# Mighty_GCD.net
KiCad netlist of a schematic drawn in EAGLE
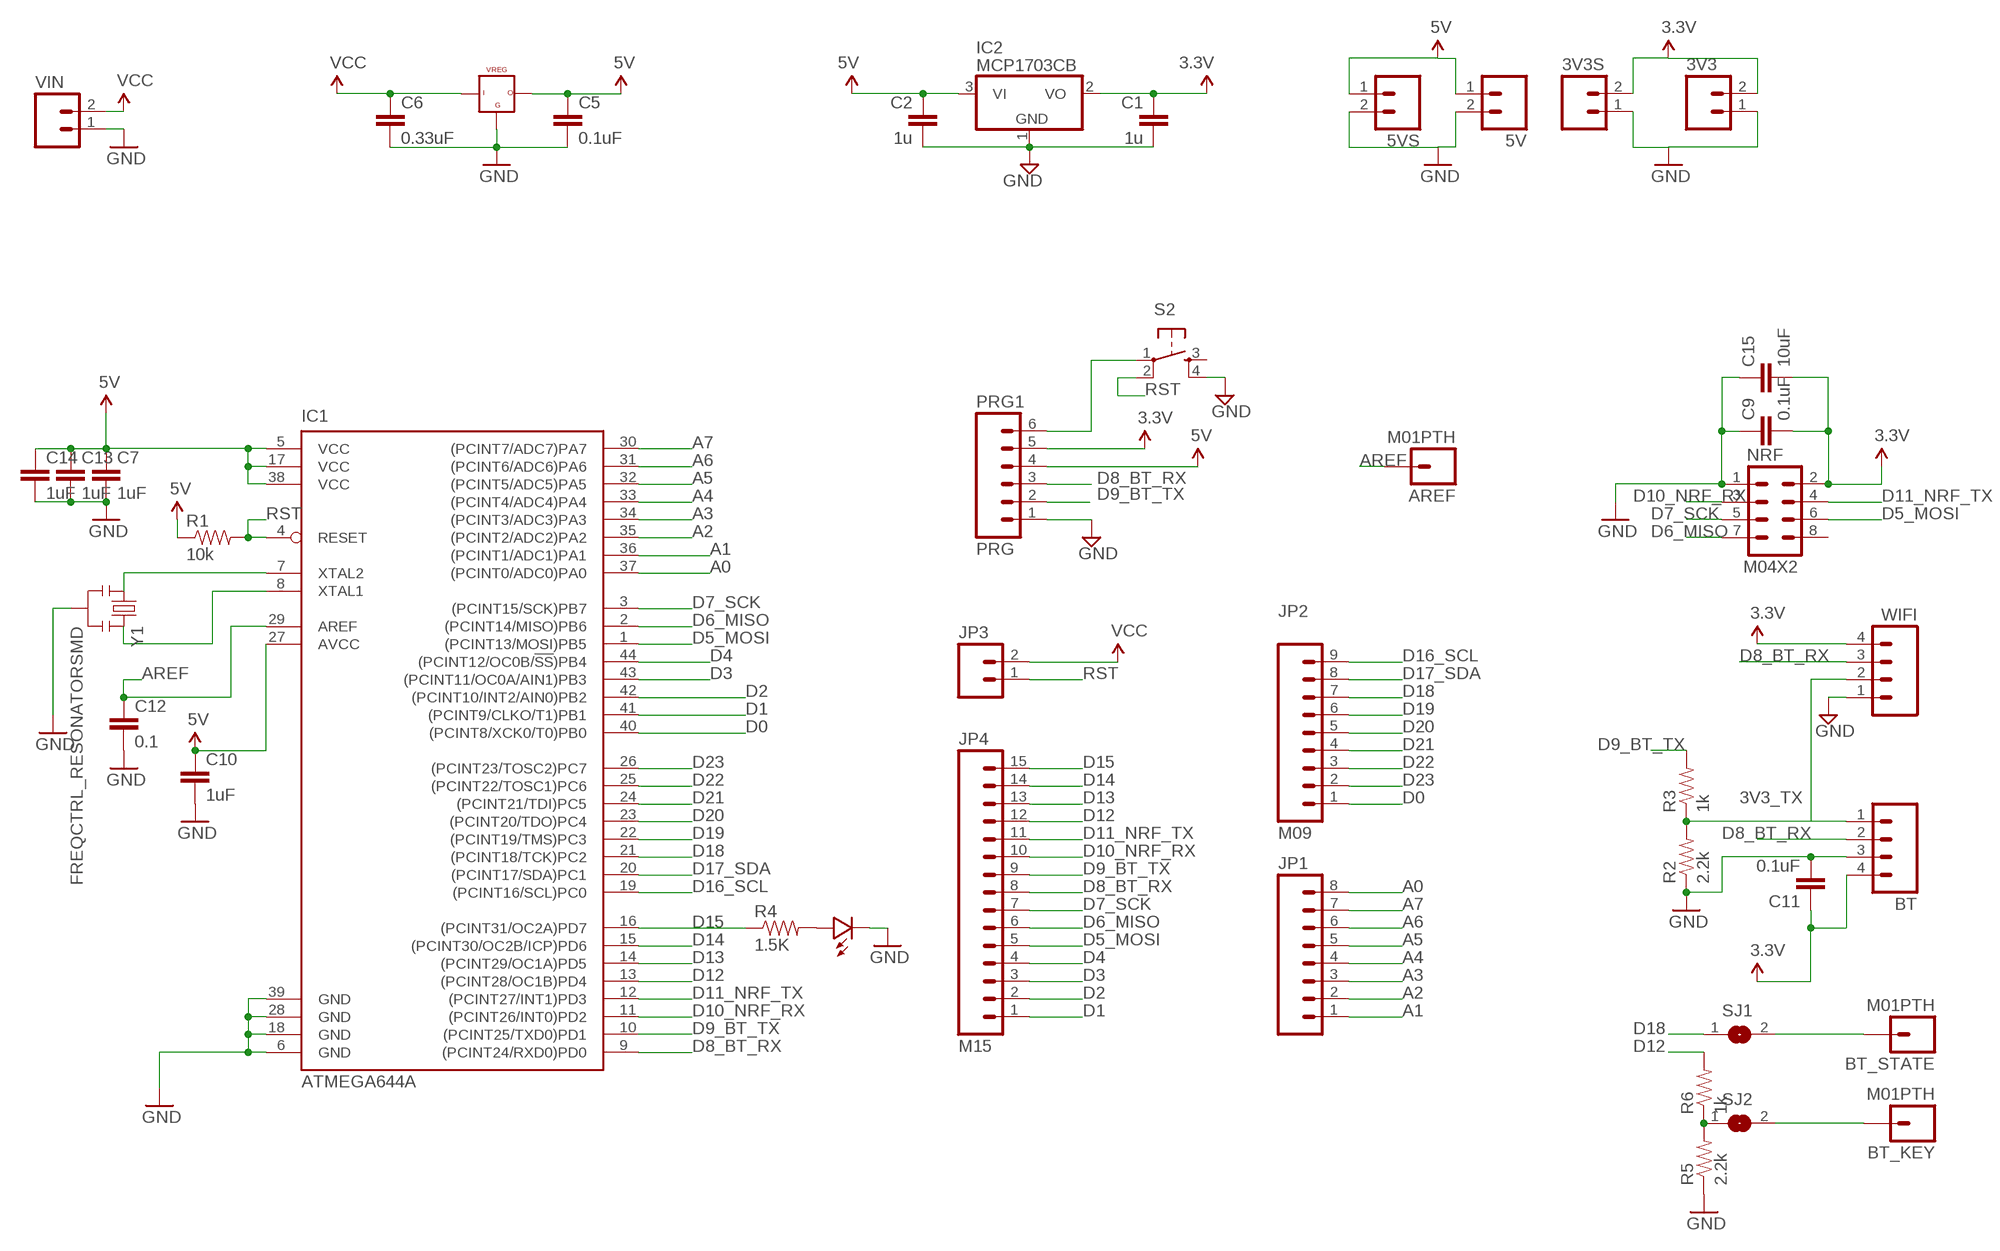
[diagram p0: schematic, sheet 1]

(export (version "E")
  (design (tool "Eeschema 10.0.6"))
  (components
    (comp (ref "3V3")
      (value "M02PTH")
      (footprint "eagle-import:1X02")
      (libsource (lib "eagle-import") (part "M02PTH"))
    )
    (comp (ref "3V3S")
      (value "M02PTH")
      (footprint "eagle-import:1X02")
      (libsource (lib "eagle-import") (part "M02PTH"))
    )
    (comp (ref "5V")
      (value "M02PTH")
      (footprint "eagle-import:1X02")
      (libsource (lib "eagle-import") (part "M02PTH"))
    )
    (comp (ref "5VS")
      (value "M02PTH")
      (footprint "eagle-import:1X02")
      (libsource (lib "eagle-import") (part "M02PTH"))
    )
    (comp (ref "AREF")
      (value "M01PTH")
      (footprint "eagle-import:1X01")
      (libsource (lib "eagle-import") (part "M01PTH"))
    )
    (comp (ref "BT")
      (value "M04PTH")
      (footprint "eagle-import:1X04")
      (libsource (lib "eagle-import") (part "M04PTH"))
    )
    (comp (ref "BT_KEY")
      (value "M01PTH")
      (footprint "eagle-import:1X01")
      (libsource (lib "eagle-import") (part "M01PTH"))
    )
    (comp (ref "BT_STATE")
      (value "M01PTH")
      (footprint "eagle-import:1X01")
      (libsource (lib "eagle-import") (part "M01PTH"))
    )
    (comp (ref "C1")
      (value "1u")
      (footprint "eagle-import:0805")
      (libsource (lib "eagle-import") (part "CAP0805"))
    )
    (comp (ref "C2")
      (value "1u")
      (footprint "eagle-import:0805")
      (libsource (lib "eagle-import") (part "CAP0805"))
    )
    (comp (ref "C5")
      (value "0.1uF")
      (footprint "eagle-import:0805")
      (libsource (lib "eagle-import") (part "SparkFun-Capacitors_CAP0805"))
    )
    (comp (ref "C6")
      (value "0.33uF")
      (footprint "eagle-import:0805")
      (libsource (lib "eagle-import") (part "SparkFun-Capacitors_CAP0805"))
    )
    (comp (ref "C7")
      (value "1uF")
      (footprint "eagle-import:0805")
      (libsource (lib "eagle-import") (part "SparkFun-Capacitors_CAP0805"))
    )
    (comp (ref "C9")
      (value "0.1uF")
      (footprint "eagle-import:0805")
      (libsource (lib "eagle-import") (part "SparkFun-Capacitors_CAP0805"))
    )
    (comp (ref "C10")
      (value "1uF")
      (footprint "eagle-import:0805")
      (libsource (lib "eagle-import") (part "SparkFun-Capacitors_CAP0805"))
    )
    (comp (ref "C11")
      (value "0.1uF")
      (footprint "eagle-import:0805")
      (libsource (lib "eagle-import") (part "SparkFun-Capacitors_CAP0805"))
    )
    (comp (ref "C12")
      (value "0.1")
      (footprint "eagle-import:0805")
      (libsource (lib "eagle-import") (part "CAP0805"))
    )
    (comp (ref "C13")
      (value "1uF")
      (footprint "eagle-import:0805")
      (libsource (lib "eagle-import") (part "SparkFun-Capacitors_CAP0805"))
    )
    (comp (ref "C14")
      (value "1uF")
      (footprint "eagle-import:0805")
      (libsource (lib "eagle-import") (part "SparkFun-Capacitors_CAP0805"))
    )
    (comp (ref "C15")
      (value "10uF")
      (footprint "eagle-import:0805")
      (libsource (lib "eagle-import") (part "SparkFun-Capacitors_CAP0805"))
    )
    (comp (ref "IC1")
      (value "ATMEGA644A")
      (footprint "eagle-import:TQFP44")
      (fields (field (name "MPN") "ATMEGA644PV-10AU"))
      (libsource (lib "eagle-import") (part "ATMEGA644A"))
    )
    (comp (ref "IC2")
      (value "MCP1703CB")
      (footprint "eagle-import:SOT23")
      (libsource (lib "eagle-import") (part "MCP1703CB"))
    )
    (comp (ref "JP1")
      (value "M081X08")
      (footprint "eagle-import:1X08")
      (libsource (lib "eagle-import") (part "M081X08"))
    )
    (comp (ref "JP2")
      (value "M09")
      (footprint "eagle-import:1X09")
      (libsource (lib "eagle-import") (part "M09"))
    )
    (comp (ref "JP3")
      (value "M02PTH")
      (footprint "eagle-import:1X02")
      (libsource (lib "eagle-import") (part "M02PTH"))
    )
    (comp (ref "JP4")
      (value "M15")
      (footprint "eagle-import:1X15")
      (libsource (lib "eagle-import") (part "M15"))
    )
    (comp (ref "NRF")
      (value "M04X2")
      (footprint "eagle-import:2X4")
      (libsource (lib "eagle-import") (part "M04X2"))
    )
    (comp (ref "PRG1")
      (value "PRG")
      (footprint "eagle-import:1X06")
      (libsource (lib "eagle-import") (part "M06SIP"))
    )
    (comp (ref "R1")
      (value "10k")
      (footprint "eagle-import:0805")
      (libsource (lib "eagle-import") (part "RESISTOR0805-RES"))
    )
    (comp (ref "R2")
      (value "2.2k")
      (footprint "eagle-import:0805")
      (libsource (lib "eagle-import") (part "RESISTOR0805-RES"))
    )
    (comp (ref "R3")
      (value "1k")
      (footprint "eagle-import:0805")
      (libsource (lib "eagle-import") (part "RESISTOR0805-RES"))
    )
    (comp (ref "R4")
      (value "1.5K")
      (footprint "eagle-import:0805")
      (libsource (lib "eagle-import") (part "RESISTOR0805-RES"))
    )
    (comp (ref "R5")
      (value "2.2k")
      (footprint "eagle-import:0805")
      (libsource (lib "eagle-import") (part "RESISTOR0805-RES"))
    )
    (comp (ref "R6")
      (value "1k")
      (footprint "eagle-import:0805")
      (libsource (lib "eagle-import") (part "RESISTOR0805-RES"))
    )
    (comp (ref "S2")
      (value "TAC_SWITCHSMD")
      (footprint "eagle-import:TACTILE_SWITCH_SMD")
      (libsource (lib "eagle-import") (part "TAC_SWITCHSMD"))
    )
    (comp (ref "SJ1") (value "SJ") (footprint "eagle-import:SJ") (libsource (lib "eagle-import") (part "SJ")))
    (comp (ref "SJ2") (value "SJ") (footprint "eagle-import:SJ") (libsource (lib "eagle-import") (part "SJ")))
    (comp (ref "U$5")
      (value "VREG_5V")
      (footprint "eagle-import:DPACK")
      (libsource (lib "eagle-import") (part "VREG_5V"))
    )
    (comp (ref "U$14")
      (value "LED0805")
      (footprint "eagle-import:0805-LED")
      (libsource (lib "eagle-import") (part "LED0805"))
    )
    (comp (ref "VIN")
      (value "M02PTH")
      (footprint "eagle-import:1X02")
      (libsource (lib "eagle-import") (part "M02PTH"))
    )
    (comp (ref "WIFI")
      (value "M04PTH")
      (footprint "eagle-import:1X04")
      (libsource (lib "eagle-import") (part "M04PTH"))
    )
    (comp (ref "Y1")
      (value "FREQCTRL_RESONATORSMD")
      (footprint "eagle-import:FREQCTRL_RESONATOR-SMD")
      (libsource (lib "eagle-import") (part "FREQCTRL_RESONATORSMD"))
    )
  )
  (nets
    (net (code "1") (name "/3V3_TX") (class "Default")
      (node (ref "BT") (pin "1") (pinfunction "1_1") (pintype "passive"))
      (node (ref "R2") (pin "2") (pinfunction "2_2") (pintype "passive"))
      (node (ref "R3") (pin "1") (pinfunction "1_1") (pintype "passive"))
      (node (ref "WIFI") (pin "2") (pinfunction "2_2") (pintype "passive"))
    )
    (net (code "2") (name "/A0") (class "Default")
      (node (ref "IC1") (pin "37") (pinfunction "(PCINT0/ADC0)PA0_37") (pintype "bidirectional"))
      (node (ref "JP1") (pin "8") (pinfunction "8_8") (pintype "passive"))
    )
    (net (code "3") (name "/A1") (class "Default")
      (node (ref "IC1") (pin "36") (pinfunction "(PCINT1/ADC1)PA1_36") (pintype "bidirectional"))
      (node (ref "JP1") (pin "1") (pinfunction "1_1") (pintype "passive"))
    )
    (net (code "4") (name "/A2") (class "Default")
      (node (ref "IC1") (pin "35") (pinfunction "(PCINT2/ADC2)PA2_35") (pintype "bidirectional"))
      (node (ref "JP1") (pin "2") (pinfunction "2_2") (pintype "passive"))
    )
    (net (code "5") (name "/A3") (class "Default")
      (node (ref "IC1") (pin "34") (pinfunction "(PCINT3/ADC3)PA3_34") (pintype "bidirectional"))
      (node (ref "JP1") (pin "3") (pinfunction "3_3") (pintype "passive"))
    )
    (net (code "6") (name "/A4") (class "Default")
      (node (ref "IC1") (pin "33") (pinfunction "(PCINT4/ADC4)PA4_33") (pintype "bidirectional"))
      (node (ref "JP1") (pin "4") (pinfunction "4_4") (pintype "passive"))
    )
    (net (code "7") (name "/A5") (class "Default")
      (node (ref "IC1") (pin "32") (pinfunction "(PCINT5/ADC5)PA5_32") (pintype "bidirectional"))
      (node (ref "JP1") (pin "5") (pinfunction "5_5") (pintype "passive"))
    )
    (net (code "8") (name "/A6") (class "Default")
      (node (ref "IC1") (pin "31") (pinfunction "(PCINT6/ADC6)PA6_31") (pintype "bidirectional"))
      (node (ref "JP1") (pin "6") (pinfunction "6_6") (pintype "passive"))
    )
    (net (code "9") (name "/A7") (class "Default")
      (node (ref "IC1") (pin "30") (pinfunction "(PCINT7/ADC7)PA7_30") (pintype "bidirectional"))
      (node (ref "JP1") (pin "7") (pinfunction "7_7") (pintype "passive"))
    )
    (net (code "10") (name "/AREF") (class "Default")
      (node (ref "AREF") (pin "1") (pinfunction "1_1") (pintype "passive"))
      (node (ref "C12") (pin "1") (pinfunction "1_1") (pintype "passive"))
      (node (ref "IC1") (pin "29") (pinfunction "AREF_29") (pintype "passive"))
    )
    (net (code "11") (name "/D0") (class "Default")
      (node (ref "IC1") (pin "40") (pinfunction "(PCINT8/XCK0/T0)PB0_40") (pintype "bidirectional"))
      (node (ref "JP2") (pin "1") (pinfunction "1_1") (pintype "passive"))
    )
    (net (code "12") (name "/D1") (class "Default")
      (node (ref "IC1") (pin "41") (pinfunction "(PCINT9/CLKO/T1)PB1_41") (pintype "bidirectional"))
      (node (ref "JP4") (pin "1") (pinfunction "1_1") (pintype "passive"))
    )
    (net (code "13") (name "/D2") (class "Default")
      (node (ref "IC1") (pin "42") (pinfunction "(PCINT10/INT2/AIN0)PB2_42") (pintype "bidirectional"))
      (node (ref "JP4") (pin "2") (pinfunction "2_2") (pintype "passive"))
    )
    (net (code "14") (name "/D3") (class "Default")
      (node (ref "IC1") (pin "43") (pinfunction "(PCINT11/OC0A/AIN1)PB3_43") (pintype "bidirectional"))
      (node (ref "JP4") (pin "3") (pinfunction "3_3") (pintype "passive"))
    )
    (net (code "15") (name "/D4") (class "Default")
      (node (ref "IC1") (pin "44") (pinfunction "(PCINT12/OC0B/~{SS})PB4_44") (pintype "bidirectional"))
      (node (ref "JP4") (pin "4") (pinfunction "4_4") (pintype "passive"))
    )
    (net (code "16") (name "/D5_MOSI") (class "Default")
      (node (ref "IC1") (pin "1") (pinfunction "(PCINT13/MOSI)PB5_1") (pintype "bidirectional"))
      (node (ref "JP4") (pin "5") (pinfunction "5_5") (pintype "passive"))
      (node (ref "NRF") (pin "6") (pinfunction "6_6") (pintype "passive"))
    )
    (net (code "17") (name "/D6_MISO") (class "Default")
      (node (ref "IC1") (pin "2") (pinfunction "(PCINT14/MISO)PB6_2") (pintype "bidirectional"))
      (node (ref "JP4") (pin "6") (pinfunction "6_6") (pintype "passive"))
      (node (ref "NRF") (pin "7") (pinfunction "7_7") (pintype "passive"))
    )
    (net (code "18") (name "/D7_SCK") (class "Default")
      (node (ref "IC1") (pin "3") (pinfunction "(PCINT15/SCK)PB7_3") (pintype "bidirectional"))
      (node (ref "JP4") (pin "7") (pinfunction "7_7") (pintype "passive"))
      (node (ref "NRF") (pin "5") (pinfunction "5_5") (pintype "passive"))
    )
    (net (code "19") (name "/D8_BT_RX") (class "Default")
      (node (ref "BT") (pin "2") (pinfunction "2_2") (pintype "passive"))
      (node (ref "IC1") (pin "9") (pinfunction "(PCINT24/RXD0)PD0_9") (pintype "bidirectional"))
      (node (ref "JP4") (pin "8") (pinfunction "8_8") (pintype "passive"))
      (node (ref "PRG1") (pin "3") (pinfunction "3_3") (pintype "passive"))
      (node (ref "WIFI") (pin "3") (pinfunction "3_3") (pintype "passive"))
    )
    (net (code "20") (name "/D9_BT_TX") (class "Default")
      (node (ref "IC1") (pin "10") (pinfunction "(PCINT25/TXD0)PD1_10") (pintype "bidirectional"))
      (node (ref "JP4") (pin "9") (pinfunction "9_9") (pintype "passive"))
      (node (ref "PRG1") (pin "2") (pinfunction "2_2") (pintype "passive"))
      (node (ref "R3") (pin "2") (pinfunction "2_2") (pintype "passive"))
    )
    (net (code "21") (name "/D10_NRF_RX") (class "Default")
      (node (ref "IC1") (pin "11") (pinfunction "(PCINT26/INT0)PD2_11") (pintype "bidirectional"))
      (node (ref "JP4") (pin "10") (pinfunction "10_10") (pintype "passive"))
      (node (ref "NRF") (pin "3") (pinfunction "3_3") (pintype "passive"))
    )
    (net (code "22") (name "/D11_NRF_TX") (class "Default")
      (node (ref "IC1") (pin "12") (pinfunction "(PCINT27/INT1)PD3_12") (pintype "bidirectional"))
      (node (ref "JP4") (pin "11") (pinfunction "11_11") (pintype "passive"))
      (node (ref "NRF") (pin "4") (pinfunction "4_4") (pintype "passive"))
    )
    (net (code "23") (name "/D12") (class "Default")
      (node (ref "IC1") (pin "13") (pinfunction "(PCINT28/OC1B)PD4_13") (pintype "bidirectional"))
      (node (ref "JP4") (pin "12") (pinfunction "12_12") (pintype "passive"))
      (node (ref "R6") (pin "2") (pinfunction "2_2") (pintype "passive"))
    )
    (net (code "24") (name "/D13") (class "Default")
      (node (ref "IC1") (pin "14") (pinfunction "(PCINT29/OC1A)PD5_14") (pintype "bidirectional"))
      (node (ref "JP4") (pin "13") (pinfunction "13_13") (pintype "passive"))
    )
    (net (code "25") (name "/D14") (class "Default")
      (node (ref "IC1") (pin "15") (pinfunction "(PCINT30/OC2B/ICP)PD6_15") (pintype "bidirectional"))
      (node (ref "JP4") (pin "14") (pinfunction "14_14") (pintype "passive"))
    )
    (net (code "26") (name "/D15") (class "Default")
      (node (ref "IC1") (pin "16") (pinfunction "(PCINT31/OC2A)PD7_16") (pintype "bidirectional"))
      (node (ref "JP4") (pin "15") (pinfunction "15_15") (pintype "passive"))
      (node (ref "R4") (pin "1") (pinfunction "1_1") (pintype "passive"))
    )
    (net (code "27") (name "/D16_SCL") (class "Default")
      (node (ref "IC1") (pin "19") (pinfunction "(PCINT16/SCL)PC0_19") (pintype "output"))
      (node (ref "JP2") (pin "9") (pinfunction "9_9") (pintype "passive"))
    )
    (net (code "28") (name "/D17_SDA") (class "Default")
      (node (ref "IC1") (pin "20") (pinfunction "(PCINT17/SDA)PC1_20") (pintype "output"))
      (node (ref "JP2") (pin "8") (pinfunction "8_8") (pintype "passive"))
    )
    (net (code "29") (name "/D18") (class "Default")
      (node (ref "IC1") (pin "21") (pinfunction "(PCINT18/TCK)PC2_21") (pintype "output"))
      (node (ref "JP2") (pin "7") (pinfunction "7_7") (pintype "passive"))
      (node (ref "SJ1") (pin "1") (pinfunction "1_1") (pintype "passive"))
    )
    (net (code "30") (name "/D19") (class "Default")
      (node (ref "IC1") (pin "22") (pinfunction "(PCINT19/TMS)PC3_22") (pintype "output"))
      (node (ref "JP2") (pin "6") (pinfunction "6_6") (pintype "passive"))
    )
    (net (code "31") (name "/D20") (class "Default")
      (node (ref "IC1") (pin "23") (pinfunction "(PCINT20/TDO)PC4_23") (pintype "output"))
      (node (ref "JP2") (pin "5") (pinfunction "5_5") (pintype "passive"))
    )
    (net (code "32") (name "/D21") (class "Default")
      (node (ref "IC1") (pin "24") (pinfunction "(PCINT21/TDI)PC5_24") (pintype "output"))
      (node (ref "JP2") (pin "4") (pinfunction "4_4") (pintype "passive"))
    )
    (net (code "33") (name "/D22") (class "Default")
      (node (ref "IC1") (pin "25") (pinfunction "(PCINT22/TOSC1)PC6_25") (pintype "output"))
      (node (ref "JP2") (pin "3") (pinfunction "3_3") (pintype "passive"))
    )
    (net (code "34") (name "/D23") (class "Default")
      (node (ref "IC1") (pin "26") (pinfunction "(PCINT23/TOSC2)PC7_26") (pintype "output"))
      (node (ref "JP2") (pin "2") (pinfunction "2_2") (pintype "passive"))
    )
    (net (code "35") (name "/RST") (class "Default")
      (node (ref "IC1") (pin "4") (pinfunction "RESET_4") (pintype "input"))
      (node (ref "JP3") (pin "1") (pinfunction "1_1") (pintype "passive"))
      (node (ref "R1") (pin "2") (pinfunction "2_2") (pintype "passive"))
      (node (ref "S2") (pin "2") (pinfunction "2_2") (pintype "passive"))
    )
    (net (code "36") (name "3.3V") (class "Default")
      (node (ref "3V3") (pin "2") (pinfunction "2_2") (pintype "passive"))
      (node (ref "3V3S") (pin "2") (pinfunction "2_2") (pintype "passive"))
      (node (ref "BT") (pin "4") (pinfunction "4_4") (pintype "passive"))
      (node (ref "C1") (pin "1") (pinfunction "1_1") (pintype "passive"))
      (node (ref "C11") (pin "1") (pinfunction "1_1") (pintype "passive"))
      (node (ref "C15") (pin "2") (pinfunction "2_2") (pintype "passive"))
      (node (ref "C9") (pin "2") (pinfunction "2_2") (pintype "passive"))
      (node (ref "IC2") (pin "2") (pinfunction "VO_2") (pintype "passive"))
      (node (ref "NRF") (pin "2") (pinfunction "2_2") (pintype "passive"))
      (node (ref "PRG1") (pin "5") (pinfunction "5_5") (pintype "passive"))
      (node (ref "WIFI") (pin "4") (pinfunction "4_4") (pintype "passive"))
    )
    (net (code "37") (name "5V") (class "Default")
      (node (ref "5V") (pin "1") (pinfunction "1_1") (pintype "passive"))
      (node (ref "5VS") (pin "1") (pinfunction "1_1") (pintype "passive"))
      (node (ref "C10") (pin "1") (pinfunction "1_1") (pintype "passive"))
      (node (ref "C13") (pin "1") (pinfunction "1_1") (pintype "passive"))
      (node (ref "C14") (pin "1") (pinfunction "1_1") (pintype "passive"))
      (node (ref "C2") (pin "1") (pinfunction "1_1") (pintype "passive"))
      (node (ref "C5") (pin "1") (pinfunction "1_1") (pintype "passive"))
      (node (ref "C7") (pin "1") (pinfunction "1_1") (pintype "passive"))
      (node (ref "IC1") (pin "17") (pinfunction "VCC_17") (pintype "power_in"))
      (node (ref "IC1") (pin "27") (pinfunction "AVCC_27") (pintype "power_in"))
      (node (ref "IC1") (pin "38") (pinfunction "VCC_38") (pintype "power_in"))
      (node (ref "IC1") (pin "5") (pinfunction "VCC_5") (pintype "power_in"))
      (node (ref "IC2") (pin "3") (pinfunction "VI_3") (pintype "input"))
      (node (ref "PRG1") (pin "4") (pinfunction "4_4") (pintype "passive"))
      (node (ref "R1") (pin "1") (pinfunction "1_1") (pintype "passive"))
      (node (ref "U$5") (pin "3") (pinfunction "3_3") (pintype "bidirectional"))
    )
    (net (code "38") (name "GND") (class "Default")
      (node (ref "3V3") (pin "1") (pinfunction "1_1") (pintype "passive"))
      (node (ref "3V3S") (pin "1") (pinfunction "1_1") (pintype "passive"))
      (node (ref "5V") (pin "2") (pinfunction "2_2") (pintype "passive"))
      (node (ref "5VS") (pin "2") (pinfunction "2_2") (pintype "passive"))
      (node (ref "BT") (pin "3") (pinfunction "3_3") (pintype "passive"))
      (node (ref "C1") (pin "2") (pinfunction "2_2") (pintype "passive"))
      (node (ref "C10") (pin "2") (pinfunction "2_2") (pintype "passive"))
      (node (ref "C11") (pin "2") (pinfunction "2_2") (pintype "passive"))
      (node (ref "C12") (pin "2") (pinfunction "2_2") (pintype "passive"))
      (node (ref "C13") (pin "2") (pinfunction "2_2") (pintype "passive"))
      (node (ref "C14") (pin "2") (pinfunction "2_2") (pintype "passive"))
      (node (ref "C15") (pin "1") (pinfunction "1_1") (pintype "passive"))
      (node (ref "C2") (pin "2") (pinfunction "2_2") (pintype "passive"))
      (node (ref "C5") (pin "2") (pinfunction "2_2") (pintype "passive"))
      (node (ref "C6") (pin "2") (pinfunction "2_2") (pintype "passive"))
      (node (ref "C7") (pin "2") (pinfunction "2_2") (pintype "passive"))
      (node (ref "C9") (pin "1") (pinfunction "1_1") (pintype "passive"))
      (node (ref "IC1") (pin "18") (pinfunction "GND_18") (pintype "power_in"))
      (node (ref "IC1") (pin "28") (pinfunction "GND_28") (pintype "power_in"))
      (node (ref "IC1") (pin "39") (pinfunction "GND_39") (pintype "power_in"))
      (node (ref "IC1") (pin "6") (pinfunction "GND_6") (pintype "power_in"))
      (node (ref "IC2") (pin "1") (pinfunction "GND_1") (pintype "passive"))
      (node (ref "NRF") (pin "1") (pinfunction "1_1") (pintype "passive"))
      (node (ref "PRG1") (pin "1") (pinfunction "1_1") (pintype "passive"))
      (node (ref "R2") (pin "1") (pinfunction "1_1") (pintype "passive"))
      (node (ref "R5") (pin "1") (pinfunction "1_1") (pintype "passive"))
      (node (ref "S2") (pin "4") (pinfunction "4_4") (pintype "passive"))
      (node (ref "U$14") (pin "MINUS") (pinfunction "MINUS_MINUS") (pintype "passive"))
      (node (ref "U$5") (pin "2") (pinfunction "2_2") (pintype "bidirectional"))
      (node (ref "VIN") (pin "1") (pinfunction "1_1") (pintype "passive"))
      (node (ref "WIFI") (pin "1") (pinfunction "1_1") (pintype "passive"))
      (node (ref "Y1") (pin "2") (pinfunction "2_2") (pintype "passive"))
    )
    (net (code "39") (name "Net-(BT_KEY-Pad1)") (class "Default")
      (node (ref "BT_KEY") (pin "1") (pinfunction "1_1") (pintype "passive"))
      (node (ref "SJ2") (pin "2") (pinfunction "2_2") (pintype "passive"))
    )
    (net (code "40") (name "Net-(BT_STATE-Pad1)") (class "Default")
      (node (ref "BT_STATE") (pin "1") (pinfunction "1_1") (pintype "passive"))
      (node (ref "SJ1") (pin "2") (pinfunction "2_2") (pintype "passive"))
    )
    (net (code "41") (name "Net-(IC1-XTAL1)") (class "Default")
      (node (ref "IC1") (pin "8") (pinfunction "XTAL1_8") (pintype "bidirectional"))
      (node (ref "Y1") (pin "3") (pinfunction "3_3") (pintype "passive"))
    )
    (net (code "42") (name "Net-(IC1-XTAL2)") (class "Default")
      (node (ref "IC1") (pin "7") (pinfunction "XTAL2_7") (pintype "bidirectional"))
      (node (ref "Y1") (pin "1") (pinfunction "1_1") (pintype "passive"))
    )
    (net (code "43") (name "Net-(PRG1-Pad6)") (class "Default")
      (node (ref "PRG1") (pin "6") (pinfunction "6_6") (pintype "passive"))
      (node (ref "S2") (pin "1") (pinfunction "1_1") (pintype "passive"))
    )
    (net (code "44") (name "Net-(R4-Pad2)") (class "Default")
      (node (ref "R4") (pin "2") (pinfunction "2_2") (pintype "passive"))
      (node (ref "U$14") (pin "PLUS") (pinfunction "PLUS_PLUS") (pintype "passive"))
    )
    (net (code "45") (name "Net-(R5-Pad2)") (class "Default")
      (node (ref "R5") (pin "2") (pinfunction "2_2") (pintype "passive"))
      (node (ref "R6") (pin "1") (pinfunction "1_1") (pintype "passive"))
      (node (ref "SJ2") (pin "1") (pinfunction "1_1") (pintype "passive"))
    )
    (net (code "46") (name "VCC") (class "Default")
      (node (ref "C6") (pin "1") (pinfunction "1_1") (pintype "passive"))
      (node (ref "JP3") (pin "2") (pinfunction "2_2") (pintype "passive"))
      (node (ref "U$5") (pin "1") (pinfunction "1_1") (pintype "bidirectional"))
      (node (ref "VIN") (pin "2") (pinfunction "2_2") (pintype "passive"))
    )
    (net (code "47") (name "unconnected-(NRF-Pad8)") (class "Default")
      (node (ref "NRF") (pin "8") (pinfunction "8_8") (pintype "passive"))
    )
    (net (code "48") (name "unconnected-(S2-Pad3)") (class "Default")
      (node (ref "S2") (pin "3") (pinfunction "3_3") (pintype "passive"))
    )
  )
)
